# SCH_DRS2_TH_2023-11-22.net
KiCad netlist of a schematic drawn in EasyEDA
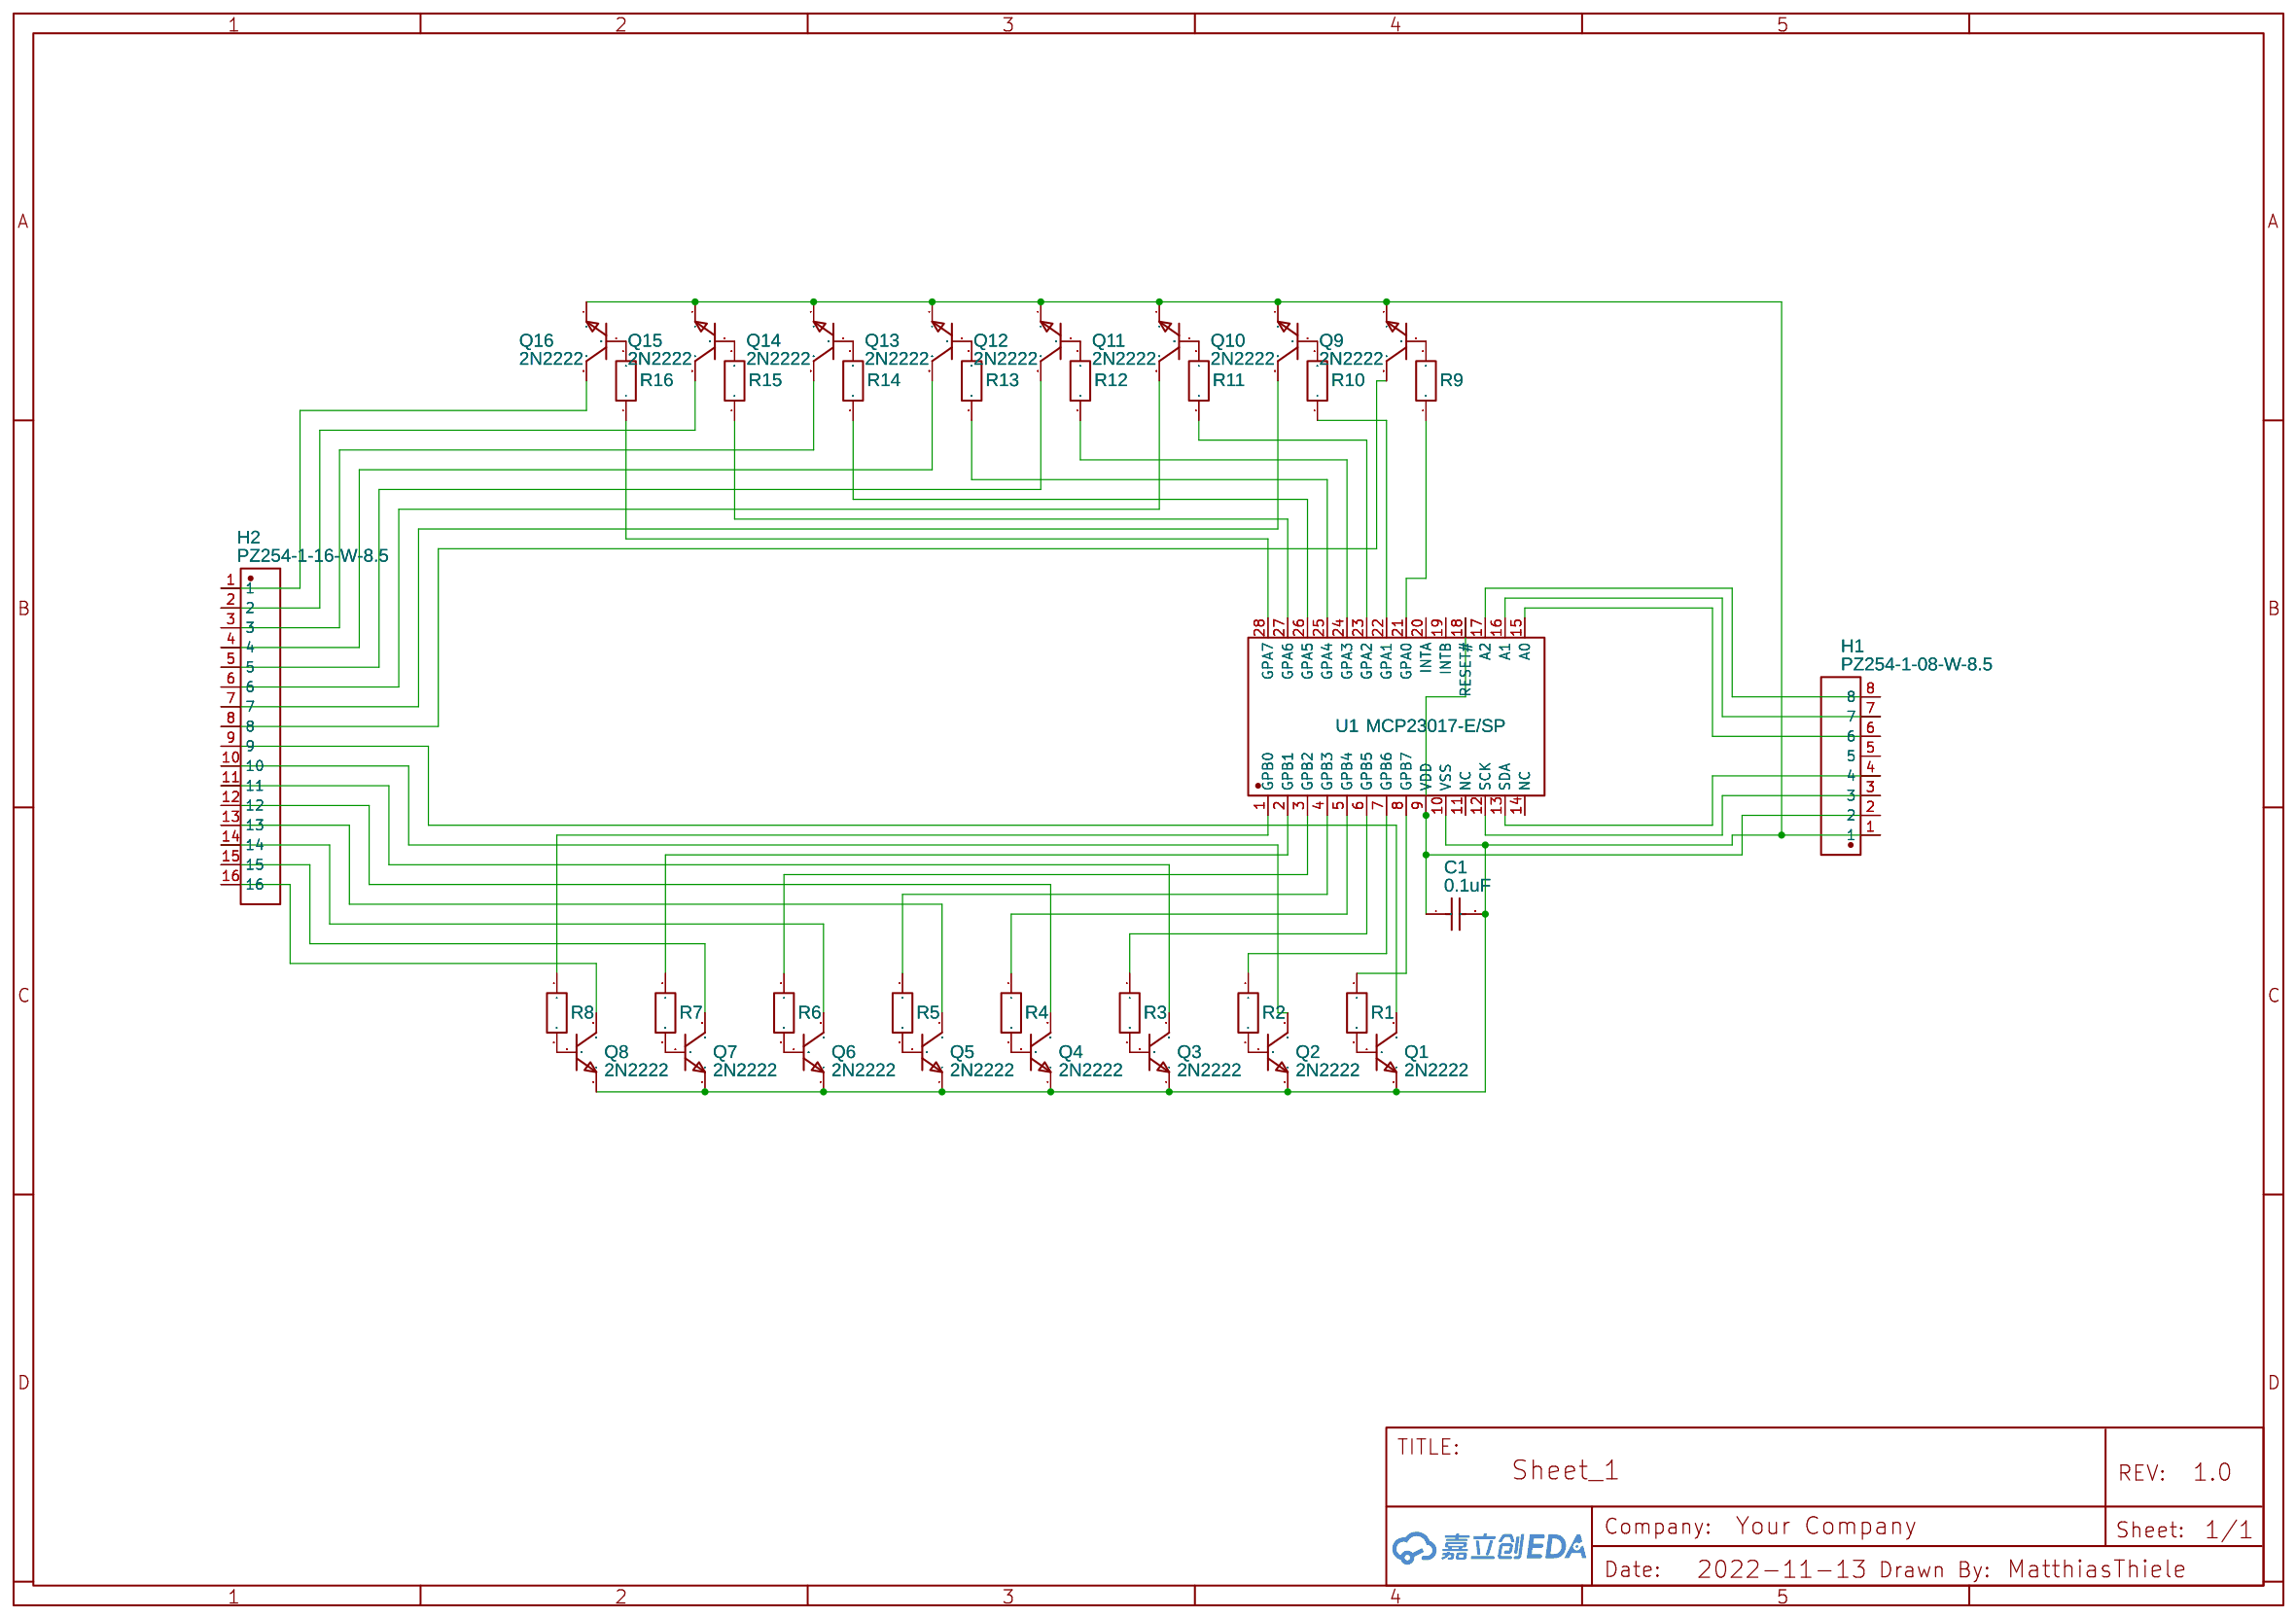
[diagram p0: schematic sheet]

(export (version "E")
  (design (tool "Eeschema 10.0.6"))
  (components
    (comp (ref "C1")
      (value "0.1uF")
      (fields (field (name "Manufacturer Part") "Ceramic capacitor0.1UF50V"))
      (libsource (lib "") (part "CERAMIC CAPACITOR_100nF"))
    )
    (comp (ref "H1")
      (value "PZ254-1-08-W-8.5")
      (fields (field (name "Manufacturer") "HCTL(华灿天禄)"))
      (libsource (lib "") (part "PZ254-1-08-W-8.5"))
    )
    (comp (ref "H2")
      (value "PZ254-1-16-W-8.5")
      (fields (field (name "Manufacturer") "HCTL(华灿天禄)"))
      (libsource (lib "") (part "PZ254-1-16-W-8.5"))
    )
    (comp (ref "Q1")
      (value "2N2222")
      (fields (field (name "Manufacturer Part") "2N2222A") (field (name "Manufacturer") "ST(先科)"))
      (libsource (lib "") (part "2N2222"))
    )
    (comp (ref "Q2")
      (value "2N2222")
      (fields (field (name "Manufacturer Part") "2N2222A") (field (name "Manufacturer") "ST(先科)"))
      (libsource (lib "") (part "2N2222"))
    )
    (comp (ref "Q3")
      (value "2N2222")
      (fields (field (name "Manufacturer Part") "2N2222A") (field (name "Manufacturer") "ST(先科)"))
      (libsource (lib "") (part "2N2222"))
    )
    (comp (ref "Q4")
      (value "2N2222")
      (fields (field (name "Manufacturer Part") "2N2222A") (field (name "Manufacturer") "ST(先科)"))
      (libsource (lib "") (part "2N2222"))
    )
    (comp (ref "Q5")
      (value "2N2222")
      (fields (field (name "Manufacturer Part") "2N2222A") (field (name "Manufacturer") "ST(先科)"))
      (libsource (lib "") (part "2N2222"))
    )
    (comp (ref "Q6")
      (value "2N2222")
      (fields (field (name "Manufacturer Part") "2N2222A") (field (name "Manufacturer") "ST(先科)"))
      (libsource (lib "") (part "2N2222"))
    )
    (comp (ref "Q7")
      (value "2N2222")
      (fields (field (name "Manufacturer Part") "2N2222A") (field (name "Manufacturer") "ST(先科)"))
      (libsource (lib "") (part "2N2222"))
    )
    (comp (ref "Q8")
      (value "2N2222")
      (fields (field (name "Manufacturer Part") "2N2222A") (field (name "Manufacturer") "ST(先科)"))
      (libsource (lib "") (part "2N2222"))
    )
    (comp (ref "Q9")
      (value "2N2222")
      (fields (field (name "Manufacturer Part") "2N2222A") (field (name "Manufacturer") "ST(先科)"))
      (libsource (lib "") (part "2N2222_1"))
    )
    (comp (ref "Q10")
      (value "2N2222")
      (fields (field (name "Manufacturer Part") "2N2222A") (field (name "Manufacturer") "ST(先科)"))
      (libsource (lib "") (part "2N2222_1"))
    )
    (comp (ref "Q11")
      (value "2N2222")
      (fields (field (name "Manufacturer Part") "2N2222A") (field (name "Manufacturer") "ST(先科)"))
      (libsource (lib "") (part "2N2222_1"))
    )
    (comp (ref "Q12")
      (value "2N2222")
      (fields (field (name "Manufacturer Part") "2N2222A") (field (name "Manufacturer") "ST(先科)"))
      (libsource (lib "") (part "2N2222_1"))
    )
    (comp (ref "Q13")
      (value "2N2222")
      (fields (field (name "Manufacturer Part") "2N2222A") (field (name "Manufacturer") "ST(先科)"))
      (libsource (lib "") (part "2N2222_1"))
    )
    (comp (ref "Q14")
      (value "2N2222")
      (fields (field (name "Manufacturer Part") "2N2222A") (field (name "Manufacturer") "ST(先科)"))
      (libsource (lib "") (part "2N2222_1"))
    )
    (comp (ref "Q15")
      (value "2N2222")
      (fields (field (name "Manufacturer Part") "2N2222A") (field (name "Manufacturer") "ST(先科)"))
      (libsource (lib "") (part "2N2222_1"))
    )
    (comp (ref "Q16")
      (value "2N2222")
      (fields (field (name "Manufacturer Part") "2N2222A") (field (name "Manufacturer") "ST(先科)"))
      (libsource (lib "") (part "2N2222_1"))
    )
    (comp (ref "R1") (value "1/4W Resistor") (libsource (lib "") (part "11Ω 1/4W Resistor_1")))
    (comp (ref "R2") (value "1/4W Resistor") (libsource (lib "") (part "11Ω 1/4W Resistor_1")))
    (comp (ref "R3") (value "1/4W Resistor") (libsource (lib "") (part "11Ω 1/4W Resistor_1")))
    (comp (ref "R4") (value "1/4W Resistor") (libsource (lib "") (part "11Ω 1/4W Resistor_1")))
    (comp (ref "R5") (value "1/4W Resistor") (libsource (lib "") (part "11Ω 1/4W Resistor_1")))
    (comp (ref "R6") (value "1/4W Resistor") (libsource (lib "") (part "11Ω 1/4W Resistor_1")))
    (comp (ref "R7") (value "1/4W Resistor") (libsource (lib "") (part "11Ω 1/4W Resistor_1")))
    (comp (ref "R8") (value "1/4W Resistor") (libsource (lib "") (part "11Ω 1/4W Resistor_1")))
    (comp (ref "R9") (value "1/4W Resistor") (libsource (lib "") (part "11Ω 1/4W Resistor")))
    (comp (ref "R10") (value "1/4W Resistor") (libsource (lib "") (part "11Ω 1/4W Resistor")))
    (comp (ref "R11") (value "1/4W Resistor") (libsource (lib "") (part "11Ω 1/4W Resistor")))
    (comp (ref "R12") (value "1/4W Resistor") (libsource (lib "") (part "11Ω 1/4W Resistor")))
    (comp (ref "R13") (value "1/4W Resistor") (libsource (lib "") (part "11Ω 1/4W Resistor")))
    (comp (ref "R14") (value "1/4W Resistor") (libsource (lib "") (part "11Ω 1/4W Resistor")))
    (comp (ref "R15") (value "1/4W Resistor") (libsource (lib "") (part "11Ω 1/4W Resistor")))
    (comp (ref "R16") (value "1/4W Resistor") (libsource (lib "") (part "11Ω 1/4W Resistor")))
    (comp (ref "U1")
      (value "MCP23017-E/SP")
      (fields (field (name "Manufacturer") "Microchip Tech"))
      (libsource (lib "") (part "MCP23017-E/SP"))
    )
  )
  (nets
    (net (code "1") (name "Net-(Q1-B)") (class "Default")
      (node (ref "Q1") (pin "2") (pinfunction "B_2") (pintype "unspecified"))
      (node (ref "R1") (pin "2") (pinfunction "2_2") (pintype "unspecified"))
    )
    (net (code "2") (name "Net-(Q1-C)") (class "Default")
      (node (ref "H2") (pin "9") (pinfunction "9_9") (pintype "unspecified"))
      (node (ref "Q1") (pin "3") (pinfunction "C_3") (pintype "unspecified"))
    )
    (net (code "3") (name "Net-(Q1-E)") (class "Default")
      (node (ref "C1") (pin "2") (pinfunction "2_2") (pintype "input"))
      (node (ref "H1") (pin "1") (pinfunction "1_1") (pintype "unspecified"))
      (node (ref "Q1") (pin "1") (pinfunction "E_1") (pintype "unspecified"))
      (node (ref "Q10") (pin "1") (pinfunction "E_1") (pintype "unspecified"))
      (node (ref "Q11") (pin "1") (pinfunction "E_1") (pintype "unspecified"))
      (node (ref "Q12") (pin "1") (pinfunction "E_1") (pintype "unspecified"))
      (node (ref "Q13") (pin "1") (pinfunction "E_1") (pintype "unspecified"))
      (node (ref "Q14") (pin "1") (pinfunction "E_1") (pintype "unspecified"))
      (node (ref "Q15") (pin "1") (pinfunction "E_1") (pintype "unspecified"))
      (node (ref "Q16") (pin "1") (pinfunction "E_1") (pintype "unspecified"))
      (node (ref "Q2") (pin "1") (pinfunction "E_1") (pintype "unspecified"))
      (node (ref "Q3") (pin "1") (pinfunction "E_1") (pintype "unspecified"))
      (node (ref "Q4") (pin "1") (pinfunction "E_1") (pintype "unspecified"))
      (node (ref "Q5") (pin "1") (pinfunction "E_1") (pintype "unspecified"))
      (node (ref "Q6") (pin "1") (pinfunction "E_1") (pintype "unspecified"))
      (node (ref "Q7") (pin "1") (pinfunction "E_1") (pintype "unspecified"))
      (node (ref "Q8") (pin "1") (pinfunction "E_1") (pintype "unspecified"))
      (node (ref "Q9") (pin "1") (pinfunction "E_1") (pintype "unspecified"))
      (node (ref "U1") (pin "10") (pinfunction "VSS_10") (pintype "unspecified"))
    )
    (net (code "4") (name "Net-(Q2-B)") (class "Default")
      (node (ref "Q2") (pin "2") (pinfunction "B_2") (pintype "unspecified"))
      (node (ref "R2") (pin "2") (pinfunction "2_2") (pintype "unspecified"))
    )
    (net (code "5") (name "Net-(Q2-C)") (class "Default")
      (node (ref "H2") (pin "10") (pinfunction "10_10") (pintype "unspecified"))
      (node (ref "Q2") (pin "3") (pinfunction "C_3") (pintype "unspecified"))
    )
    (net (code "6") (name "Net-(Q3-B)") (class "Default")
      (node (ref "Q3") (pin "2") (pinfunction "B_2") (pintype "unspecified"))
      (node (ref "R3") (pin "2") (pinfunction "2_2") (pintype "unspecified"))
    )
    (net (code "7") (name "Net-(Q3-C)") (class "Default")
      (node (ref "H2") (pin "11") (pinfunction "11_11") (pintype "unspecified"))
      (node (ref "Q3") (pin "3") (pinfunction "C_3") (pintype "unspecified"))
    )
    (net (code "8") (name "Net-(Q4-B)") (class "Default")
      (node (ref "Q4") (pin "2") (pinfunction "B_2") (pintype "unspecified"))
      (node (ref "R4") (pin "2") (pinfunction "2_2") (pintype "unspecified"))
    )
    (net (code "9") (name "Net-(Q4-C)") (class "Default")
      (node (ref "H2") (pin "12") (pinfunction "12_12") (pintype "unspecified"))
      (node (ref "Q4") (pin "3") (pinfunction "C_3") (pintype "unspecified"))
    )
    (net (code "10") (name "Net-(Q5-B)") (class "Default")
      (node (ref "Q5") (pin "2") (pinfunction "B_2") (pintype "unspecified"))
      (node (ref "R5") (pin "2") (pinfunction "2_2") (pintype "unspecified"))
    )
    (net (code "11") (name "Net-(Q5-C)") (class "Default")
      (node (ref "H2") (pin "13") (pinfunction "13_13") (pintype "unspecified"))
      (node (ref "Q5") (pin "3") (pinfunction "C_3") (pintype "unspecified"))
    )
    (net (code "12") (name "Net-(Q6-B)") (class "Default")
      (node (ref "Q6") (pin "2") (pinfunction "B_2") (pintype "unspecified"))
      (node (ref "R6") (pin "2") (pinfunction "2_2") (pintype "unspecified"))
    )
    (net (code "13") (name "Net-(Q6-C)") (class "Default")
      (node (ref "H2") (pin "14") (pinfunction "14_14") (pintype "unspecified"))
      (node (ref "Q6") (pin "3") (pinfunction "C_3") (pintype "unspecified"))
    )
    (net (code "14") (name "Net-(Q7-B)") (class "Default")
      (node (ref "Q7") (pin "2") (pinfunction "B_2") (pintype "unspecified"))
      (node (ref "R7") (pin "2") (pinfunction "2_2") (pintype "unspecified"))
    )
    (net (code "15") (name "Net-(Q7-C)") (class "Default")
      (node (ref "H2") (pin "15") (pinfunction "15_15") (pintype "unspecified"))
      (node (ref "Q7") (pin "3") (pinfunction "C_3") (pintype "unspecified"))
    )
    (net (code "16") (name "Net-(Q8-B)") (class "Default")
      (node (ref "Q8") (pin "2") (pinfunction "B_2") (pintype "unspecified"))
      (node (ref "R8") (pin "2") (pinfunction "2_2") (pintype "unspecified"))
    )
    (net (code "17") (name "Net-(Q8-C)") (class "Default")
      (node (ref "H2") (pin "16") (pinfunction "16_16") (pintype "unspecified"))
      (node (ref "Q8") (pin "3") (pinfunction "C_3") (pintype "unspecified"))
    )
    (net (code "18") (name "Net-(Q9-B)") (class "Default")
      (node (ref "Q9") (pin "2") (pinfunction "B_2") (pintype "unspecified"))
      (node (ref "R9") (pin "2") (pinfunction "2_2") (pintype "unspecified"))
    )
    (net (code "19") (name "Net-(Q9-C)") (class "Default")
      (node (ref "H2") (pin "8") (pinfunction "8_8") (pintype "unspecified"))
      (node (ref "Q9") (pin "3") (pinfunction "C_3") (pintype "unspecified"))
    )
    (net (code "20") (name "Net-(Q10-B)") (class "Default")
      (node (ref "Q10") (pin "2") (pinfunction "B_2") (pintype "unspecified"))
      (node (ref "R10") (pin "2") (pinfunction "2_2") (pintype "unspecified"))
    )
    (net (code "21") (name "Net-(Q10-C)") (class "Default")
      (node (ref "H2") (pin "7") (pinfunction "7_7") (pintype "unspecified"))
      (node (ref "Q10") (pin "3") (pinfunction "C_3") (pintype "unspecified"))
    )
    (net (code "22") (name "Net-(Q11-B)") (class "Default")
      (node (ref "Q11") (pin "2") (pinfunction "B_2") (pintype "unspecified"))
      (node (ref "R11") (pin "2") (pinfunction "2_2") (pintype "unspecified"))
    )
    (net (code "23") (name "Net-(Q11-C)") (class "Default")
      (node (ref "H2") (pin "6") (pinfunction "6_6") (pintype "unspecified"))
      (node (ref "Q11") (pin "3") (pinfunction "C_3") (pintype "unspecified"))
    )
    (net (code "24") (name "Net-(Q12-B)") (class "Default")
      (node (ref "Q12") (pin "2") (pinfunction "B_2") (pintype "unspecified"))
      (node (ref "R12") (pin "2") (pinfunction "2_2") (pintype "unspecified"))
    )
    (net (code "25") (name "Net-(Q12-C)") (class "Default")
      (node (ref "H2") (pin "5") (pinfunction "5_5") (pintype "unspecified"))
      (node (ref "Q12") (pin "3") (pinfunction "C_3") (pintype "unspecified"))
    )
    (net (code "26") (name "Net-(Q13-B)") (class "Default")
      (node (ref "Q13") (pin "2") (pinfunction "B_2") (pintype "unspecified"))
      (node (ref "R13") (pin "2") (pinfunction "2_2") (pintype "unspecified"))
    )
    (net (code "27") (name "Net-(Q13-C)") (class "Default")
      (node (ref "H2") (pin "4") (pinfunction "4_4") (pintype "unspecified"))
      (node (ref "Q13") (pin "3") (pinfunction "C_3") (pintype "unspecified"))
    )
    (net (code "28") (name "Net-(Q14-B)") (class "Default")
      (node (ref "Q14") (pin "2") (pinfunction "B_2") (pintype "unspecified"))
      (node (ref "R14") (pin "2") (pinfunction "2_2") (pintype "unspecified"))
    )
    (net (code "29") (name "Net-(Q14-C)") (class "Default")
      (node (ref "H2") (pin "3") (pinfunction "3_3") (pintype "unspecified"))
      (node (ref "Q14") (pin "3") (pinfunction "C_3") (pintype "unspecified"))
    )
    (net (code "30") (name "Net-(Q15-B)") (class "Default")
      (node (ref "Q15") (pin "2") (pinfunction "B_2") (pintype "unspecified"))
      (node (ref "R15") (pin "2") (pinfunction "2_2") (pintype "unspecified"))
    )
    (net (code "31") (name "Net-(Q15-C)") (class "Default")
      (node (ref "H2") (pin "2") (pinfunction "2_2") (pintype "unspecified"))
      (node (ref "Q15") (pin "3") (pinfunction "C_3") (pintype "unspecified"))
    )
    (net (code "32") (name "Net-(Q16-B)") (class "Default")
      (node (ref "Q16") (pin "2") (pinfunction "B_2") (pintype "unspecified"))
      (node (ref "R16") (pin "2") (pinfunction "2_2") (pintype "unspecified"))
    )
    (net (code "33") (name "Net-(Q16-C)") (class "Default")
      (node (ref "H2") (pin "1") (pinfunction "1_1") (pintype "unspecified"))
      (node (ref "Q16") (pin "3") (pinfunction "C_3") (pintype "unspecified"))
    )
    (net (code "34") (name "Net-(U1-A0)") (class "Default")
      (node (ref "H1") (pin "6") (pinfunction "6_6") (pintype "unspecified"))
      (node (ref "U1") (pin "15") (pinfunction "A0_15") (pintype "unspecified"))
    )
    (net (code "35") (name "Net-(U1-A1)") (class "Default")
      (node (ref "H1") (pin "7") (pinfunction "7_7") (pintype "unspecified"))
      (node (ref "U1") (pin "16") (pinfunction "A1_16") (pintype "unspecified"))
    )
    (net (code "36") (name "Net-(U1-A2)") (class "Default")
      (node (ref "H1") (pin "8") (pinfunction "8_8") (pintype "unspecified"))
      (node (ref "U1") (pin "17") (pinfunction "A2_17") (pintype "unspecified"))
    )
    (net (code "37") (name "Net-(U1-GPA0)") (class "Default")
      (node (ref "R9") (pin "1") (pinfunction "1_1") (pintype "unspecified"))
      (node (ref "U1") (pin "21") (pinfunction "GPA0_21") (pintype "unspecified"))
    )
    (net (code "38") (name "Net-(U1-GPA1)") (class "Default")
      (node (ref "R10") (pin "1") (pinfunction "1_1") (pintype "unspecified"))
      (node (ref "U1") (pin "22") (pinfunction "GPA1_22") (pintype "unspecified"))
    )
    (net (code "39") (name "Net-(U1-GPA2)") (class "Default")
      (node (ref "R11") (pin "1") (pinfunction "1_1") (pintype "unspecified"))
      (node (ref "U1") (pin "23") (pinfunction "GPA2_23") (pintype "unspecified"))
    )
    (net (code "40") (name "Net-(U1-GPA3)") (class "Default")
      (node (ref "R12") (pin "1") (pinfunction "1_1") (pintype "unspecified"))
      (node (ref "U1") (pin "24") (pinfunction "GPA3_24") (pintype "unspecified"))
    )
    (net (code "41") (name "Net-(U1-GPA4)") (class "Default")
      (node (ref "R13") (pin "1") (pinfunction "1_1") (pintype "unspecified"))
      (node (ref "U1") (pin "25") (pinfunction "GPA4_25") (pintype "unspecified"))
    )
    (net (code "42") (name "Net-(U1-GPA5)") (class "Default")
      (node (ref "R14") (pin "1") (pinfunction "1_1") (pintype "unspecified"))
      (node (ref "U1") (pin "26") (pinfunction "GPA5_26") (pintype "unspecified"))
    )
    (net (code "43") (name "Net-(U1-GPA6)") (class "Default")
      (node (ref "R15") (pin "1") (pinfunction "1_1") (pintype "unspecified"))
      (node (ref "U1") (pin "27") (pinfunction "GPA6_27") (pintype "unspecified"))
    )
    (net (code "44") (name "Net-(U1-GPA7)") (class "Default")
      (node (ref "R16") (pin "1") (pinfunction "1_1") (pintype "unspecified"))
      (node (ref "U1") (pin "28") (pinfunction "GPA7_28") (pintype "unspecified"))
    )
    (net (code "45") (name "Net-(U1-GPB0)") (class "Default")
      (node (ref "R8") (pin "1") (pinfunction "1_1") (pintype "unspecified"))
      (node (ref "U1") (pin "1") (pinfunction "GPB0_1") (pintype "unspecified"))
    )
    (net (code "46") (name "Net-(U1-GPB1)") (class "Default")
      (node (ref "R7") (pin "1") (pinfunction "1_1") (pintype "unspecified"))
      (node (ref "U1") (pin "2") (pinfunction "GPB1_2") (pintype "unspecified"))
    )
    (net (code "47") (name "Net-(U1-GPB2)") (class "Default")
      (node (ref "R6") (pin "1") (pinfunction "1_1") (pintype "unspecified"))
      (node (ref "U1") (pin "3") (pinfunction "GPB2_3") (pintype "unspecified"))
    )
    (net (code "48") (name "Net-(U1-GPB3)") (class "Default")
      (node (ref "R5") (pin "1") (pinfunction "1_1") (pintype "unspecified"))
      (node (ref "U1") (pin "4") (pinfunction "GPB3_4") (pintype "unspecified"))
    )
    (net (code "49") (name "Net-(U1-GPB4)") (class "Default")
      (node (ref "R4") (pin "1") (pinfunction "1_1") (pintype "unspecified"))
      (node (ref "U1") (pin "5") (pinfunction "GPB4_5") (pintype "unspecified"))
    )
    (net (code "50") (name "Net-(U1-GPB5)") (class "Default")
      (node (ref "R3") (pin "1") (pinfunction "1_1") (pintype "unspecified"))
      (node (ref "U1") (pin "6") (pinfunction "GPB5_6") (pintype "unspecified"))
    )
    (net (code "51") (name "Net-(U1-GPB6)") (class "Default")
      (node (ref "R2") (pin "1") (pinfunction "1_1") (pintype "unspecified"))
      (node (ref "U1") (pin "7") (pinfunction "GPB6_7") (pintype "unspecified"))
    )
    (net (code "52") (name "Net-(U1-GPB7)") (class "Default")
      (node (ref "R1") (pin "1") (pinfunction "1_1") (pintype "unspecified"))
      (node (ref "U1") (pin "8") (pinfunction "GPB7_8") (pintype "unspecified"))
    )
    (net (code "53") (name "Net-(U1-RESET#)") (class "Default")
      (node (ref "C1") (pin "1") (pinfunction "1_1") (pintype "input"))
      (node (ref "H1") (pin "2") (pinfunction "2_2") (pintype "unspecified"))
      (node (ref "U1") (pin "18") (pinfunction "RESET#_18") (pintype "unspecified"))
      (node (ref "U1") (pin "9") (pinfunction "VDD_9") (pintype "unspecified"))
    )
    (net (code "54") (name "Net-(U1-SCK)") (class "Default")
      (node (ref "H1") (pin "3") (pinfunction "3_3") (pintype "unspecified"))
      (node (ref "U1") (pin "12") (pinfunction "SCK_12") (pintype "unspecified"))
    )
    (net (code "55") (name "Net-(U1-SDA)") (class "Default")
      (node (ref "H1") (pin "4") (pinfunction "4_4") (pintype "unspecified"))
      (node (ref "U1") (pin "13") (pinfunction "SDA_13") (pintype "unspecified"))
    )
    (net (code "56") (name "unconnected-(H1-Pad5)") (class "Default")
      (node (ref "H1") (pin "5") (pinfunction "5_5") (pintype "unspecified"))
    )
    (net (code "57") (name "unconnected-(U1-INTA-Pad20)") (class "Default")
      (node (ref "U1") (pin "20") (pinfunction "INTA_20") (pintype "unspecified"))
    )
    (net (code "58") (name "unconnected-(U1-INTB-Pad19)") (class "Default")
      (node (ref "U1") (pin "19") (pinfunction "INTB_19") (pintype "unspecified"))
    )
    (net (code "59") (name "unconnected-(U1-NC-Pad11)") (class "Default")
      (node (ref "U1") (pin "11") (pinfunction "NC_11") (pintype "unspecified"))
    )
    (net (code "60") (name "unconnected-(U1-NC-Pad14)") (class "Default")
      (node (ref "U1") (pin "14") (pinfunction "NC_14") (pintype "unspecified"))
    )
  )
)
